# InfraredModule.net
KiCad netlist of a schematic drawn in Altium Designer
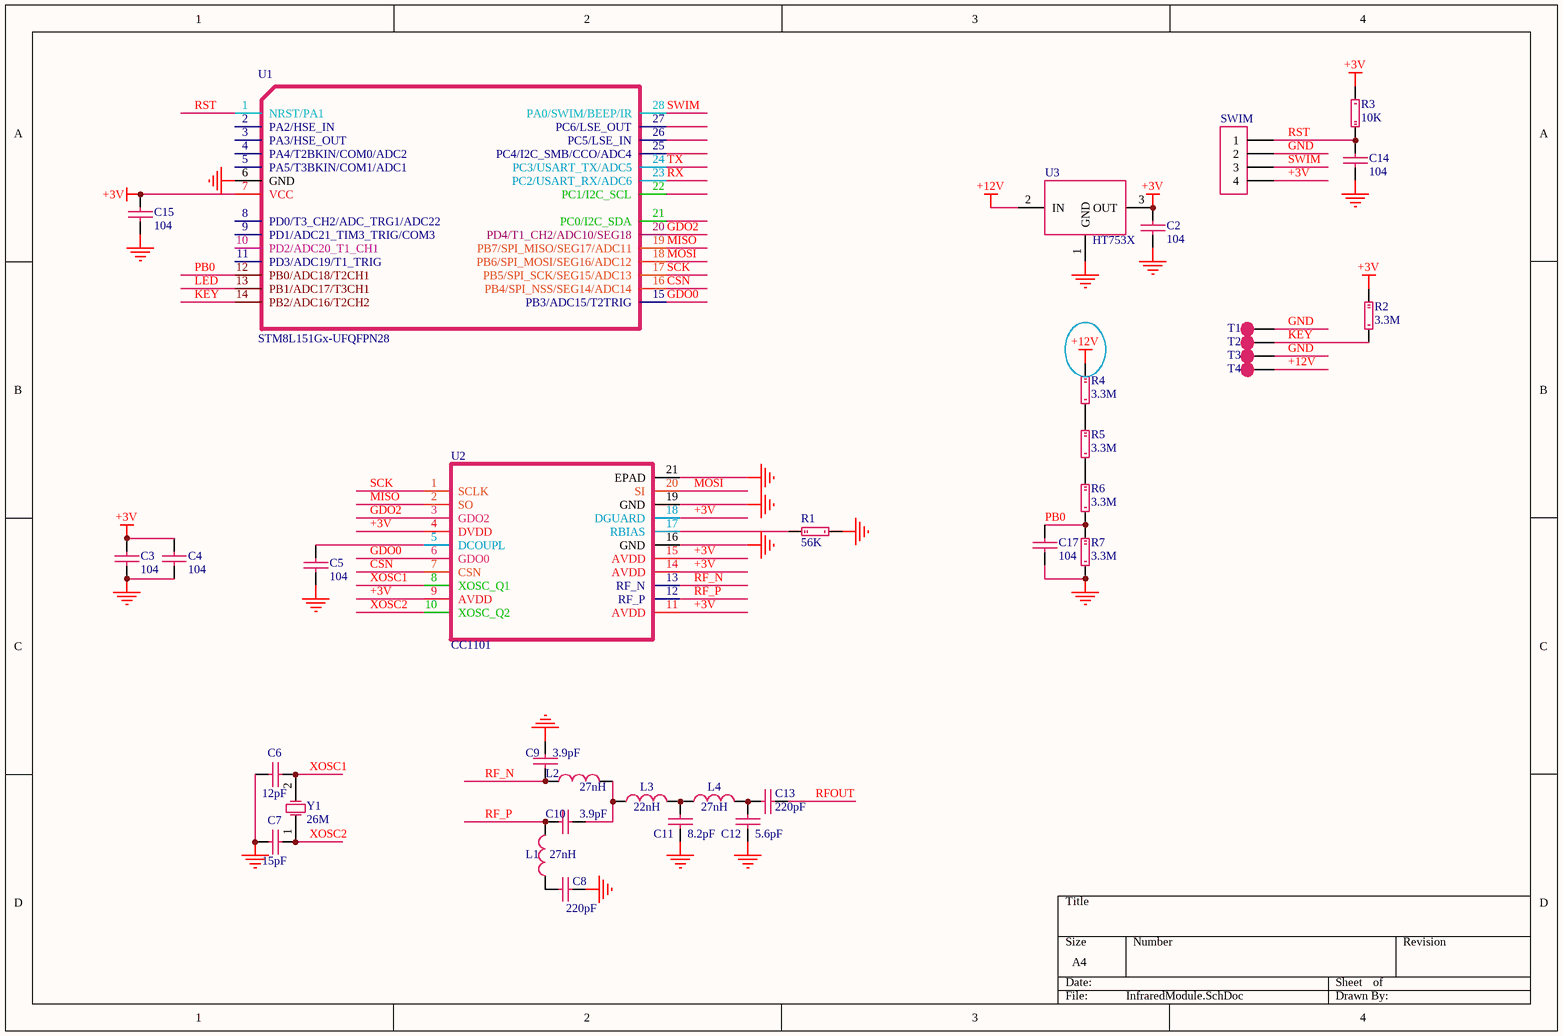
[diagram p0: InfraredModule.SchDoc]

(export (version "E")
  (design (tool "Eeschema 10.0.6"))
  (components
    (comp (ref "C2")
      (value "104")
      (footprint "C0402")
      (description "无极性电容")
      (libsource (lib "Sch_Lib") (part "CAP"))
    )
    (comp (ref "C3")
      (value "104")
      (footprint "C0402")
      (description "无极性电容")
      (libsource (lib "Sch_Lib") (part "CAP"))
    )
    (comp (ref "C4")
      (value "104")
      (footprint "C0402")
      (description "无极性电容")
      (libsource (lib "Sch_Lib") (part "CAP"))
    )
    (comp (ref "C5")
      (value "104")
      (footprint "C0402")
      (description "无极性电容")
      (libsource (lib "Sch_Lib") (part "CAP"))
    )
    (comp (ref "C6")
      (value "12pF")
      (footprint "C0402")
      (description "无极性电容")
      (libsource (lib "Sch_Lib") (part "CAP"))
    )
    (comp (ref "C7")
      (value "15pF")
      (footprint "C0402")
      (description "无极性电容")
      (libsource (lib "Sch_Lib") (part "CAP"))
    )
    (comp (ref "C8")
      (value "220pF")
      (footprint "C0402")
      (description "无极性电容")
      (libsource (lib "Sch_Lib") (part "CAP"))
    )
    (comp (ref "C9")
      (value "3.9pF")
      (footprint "C0402")
      (description "无极性电容")
      (libsource (lib "Sch_Lib") (part "CAP"))
    )
    (comp (ref "C10")
      (value "3.9pF")
      (footprint "C0402")
      (description "无极性电容")
      (libsource (lib "Sch_Lib") (part "CAP"))
    )
    (comp (ref "C11")
      (value "8.2pF")
      (footprint "C0402")
      (description "无极性电容")
      (libsource (lib "Sch_Lib") (part "CAP"))
    )
    (comp (ref "C12")
      (value "5.6pF")
      (footprint "C0402")
      (description "无极性电容")
      (libsource (lib "Sch_Lib") (part "CAP"))
    )
    (comp (ref "C13")
      (value "220pF")
      (footprint "C0402")
      (description "无极性电容")
      (libsource (lib "Sch_Lib") (part "CAP"))
    )
    (comp (ref "C14")
      (value "104")
      (footprint "C0402")
      (description "无极性电容")
      (libsource (lib "Sch_Lib") (part "CAP"))
    )
    (comp (ref "C15")
      (value "104")
      (footprint "C0402")
      (description "无极性电容")
      (libsource (lib "Sch_Lib") (part "CAP"))
    )
    (comp (ref "C17")
      (value "104")
      (footprint "C0402")
      (description "无极性电容")
      (libsource (lib "Sch_Lib") (part "CAP"))
    )
    (comp (ref "L1")
      (value "27nH")
      (footprint "L0402")
      (description "电感")
      (libsource (lib "Sch_Lib") (part "INDUCTOR"))
    )
    (comp (ref "L2")
      (value "27nH")
      (footprint "L0402")
      (description "电感")
      (libsource (lib "Sch_Lib") (part "INDUCTOR"))
    )
    (comp (ref "L3")
      (value "22nH")
      (footprint "L0402")
      (description "电感")
      (libsource (lib "Sch_Lib") (part "INDUCTOR"))
    )
    (comp (ref "L4")
      (value "27nH")
      (footprint "L0402")
      (description "电感")
      (libsource (lib "Sch_Lib") (part "INDUCTOR"))
    )
    (comp (ref "R1")
      (value "56K")
      (footprint "R0402")
      (description "贴片电阻")
      (libsource (lib "Sch_Lib") (part "RES2"))
    )
    (comp (ref "R2")
      (value "3.3M")
      (footprint "R0402")
      (description "贴片电阻")
      (libsource (lib "Sch_Lib") (part "RES2"))
    )
    (comp (ref "R3")
      (value "10K")
      (footprint "R0402")
      (description "贴片电阻")
      (libsource (lib "Sch_Lib") (part "RES2"))
    )
    (comp (ref "R4")
      (value "3.3M")
      (footprint "R0402")
      (description "贴片电阻")
      (libsource (lib "Sch_Lib") (part "RES2"))
    )
    (comp (ref "R5")
      (value "3.3M")
      (footprint "R0402")
      (description "贴片电阻")
      (libsource (lib "Sch_Lib") (part "RES2"))
    )
    (comp (ref "R6")
      (value "3.3M")
      (footprint "R0402")
      (description "贴片电阻")
      (libsource (lib "Sch_Lib") (part "RES2"))
    )
    (comp (ref "R7")
      (value "3.3M")
      (footprint "R0402")
      (description "贴片电阻")
      (libsource (lib "Sch_Lib") (part "RES2"))
    )
    (comp (ref "SWIM") (value "~") (footprint "SIP4-2MM") (libsource (lib "Sch_Lib") (part "HEADER 4X1")))
    (comp (ref "T1")
      (value "~")
      (footprint "TP")
      (description "测试点/触摸点")
      (libsource (lib "Sch_Lib") (part "TP"))
    )
    (comp (ref "T2")
      (value "~")
      (footprint "TP")
      (description "测试点/触摸点")
      (libsource (lib "Sch_Lib") (part "TP"))
    )
    (comp (ref "T3")
      (value "~")
      (footprint "TP")
      (description "测试点/触摸点")
      (libsource (lib "Sch_Lib") (part "TP"))
    )
    (comp (ref "T4")
      (value "~")
      (footprint "TP")
      (description "测试点/触摸点")
      (libsource (lib "Sch_Lib") (part "TP"))
    )
    (comp (ref "U1")
      (value "STM8L151Gx-UFQFPN28")
      (footprint "QFN28-4X4")
      (description "STM8L单片机28引脚,封装UFQFPN28")
      (libsource (lib "Sch_Lib") (part "STM8L151Gx-UFQFPN28"))
    )
    (comp (ref "U2")
      (value "CC1101")
      (footprint "QLP-20")
      (description "RF芯片 TI CC系列")
      (libsource (lib "Sch_Lib") (part "CC1101"))
    )
    (comp (ref "U3")
      (value "HT753X")
      (footprint "SOT-89")
      (description "合泰稳压芯片HT系列")
      (libsource (lib "Sch_Lib") (part "HT753X"))
    )
    (comp (ref "Y1")
      (value "26M")
      (footprint "XTAL-(3.2X2.5MM)-4P")
      (description "晶振")
      (libsource (lib "Sch_Lib") (part "XTAL"))
    )
  )
  (nets
    (net (code "1") (name "+3V") (class "Default")
      (node (ref "C15") (pin "1") (pinfunction "1_1") (pintype "passive"))
      (node (ref "C2") (pin "1") (pinfunction "1_1") (pintype "passive"))
      (node (ref "C3") (pin "1") (pinfunction "1_1") (pintype "passive"))
      (node (ref "C4") (pin "1") (pinfunction "1_1") (pintype "passive"))
      (node (ref "R2") (pin "2") (pinfunction "2_2") (pintype "passive"))
      (node (ref "R3") (pin "1") (pinfunction "1_1") (pintype "passive"))
      (node (ref "SWIM") (pin "4") (pinfunction "4_4") (pintype "passive"))
      (node (ref "U1") (pin "7") (pinfunction "VCC_7") (pintype "passive"))
      (node (ref "U2") (pin "11") (pinfunction "AVDD_11") (pintype "passive"))
      (node (ref "U2") (pin "14") (pinfunction "AVDD_14") (pintype "passive"))
      (node (ref "U2") (pin "15") (pinfunction "AVDD_15") (pintype "passive"))
      (node (ref "U2") (pin "18") (pinfunction "DGUARD_18") (pintype "passive"))
      (node (ref "U2") (pin "4") (pinfunction "DVDD_4") (pintype "passive"))
      (node (ref "U2") (pin "9") (pinfunction "AVDD_9") (pintype "passive"))
      (node (ref "U3") (pin "3") (pinfunction "OUT_3") (pintype "passive"))
    )
    (net (code "2") (name "+12V") (class "Default")
      (node (ref "R4") (pin "2") (pinfunction "2_2") (pintype "passive"))
      (node (ref "T4") (pin "1") (pinfunction "1_1") (pintype "passive"))
      (node (ref "U3") (pin "2") (pinfunction "IN_2") (pintype "passive"))
    )
    (net (code "3") (name "/CSN") (class "Default")
      (node (ref "U1") (pin "16") (pinfunction "PB4/SPI_NSS/SEG14/ADC14_16") (pintype "passive"))
      (node (ref "U2") (pin "7") (pinfunction "CSN_7") (pintype "passive"))
    )
    (net (code "4") (name "/GDO0") (class "Default")
      (node (ref "U1") (pin "15") (pinfunction "PB3/ADC15/T2TRIG_15") (pintype "passive"))
      (node (ref "U2") (pin "6") (pinfunction "GDO0_6") (pintype "passive"))
    )
    (net (code "5") (name "/GDO2") (class "Default")
      (node (ref "U1") (pin "20") (pinfunction "PD4/T1_CH2/ADC10/SEG18_20") (pintype "passive"))
      (node (ref "U2") (pin "3") (pinfunction "GDO2_3") (pintype "passive"))
    )
    (net (code "6") (name "/KEY") (class "Default")
      (node (ref "R2") (pin "1") (pinfunction "1_1") (pintype "passive"))
      (node (ref "T2") (pin "1") (pinfunction "1_1") (pintype "passive"))
      (node (ref "U1") (pin "14") (pinfunction "PB2/ADC16/T2CH2_14") (pintype "passive"))
    )
    (net (code "7") (name "/LED") (class "Default")
      (node (ref "U1") (pin "13") (pinfunction "PB1/ADC17/T3CH1_13") (pintype "passive"))
    )
    (net (code "8") (name "/MISO") (class "Default")
      (node (ref "U1") (pin "19") (pinfunction "PB7/SPI_MISO/SEG17/ADC11_19") (pintype "passive"))
      (node (ref "U2") (pin "2") (pinfunction "SO_2") (pintype "passive"))
    )
    (net (code "9") (name "/MOSI") (class "Default")
      (node (ref "U1") (pin "18") (pinfunction "PB6/SPI_MOSI/SEG16/ADC12_18") (pintype "passive"))
      (node (ref "U2") (pin "20") (pinfunction "SI_20") (pintype "passive"))
    )
    (net (code "10") (name "/PB0") (class "Default")
      (node (ref "C17") (pin "1") (pinfunction "1_1") (pintype "passive"))
      (node (ref "R6") (pin "1") (pinfunction "1_1") (pintype "passive"))
      (node (ref "R7") (pin "2") (pinfunction "2_2") (pintype "passive"))
      (node (ref "U1") (pin "12") (pinfunction "PB0/ADC18/T2CH1_12") (pintype "passive"))
    )
    (net (code "11") (name "/RFOUT") (class "Default")
      (node (ref "C13") (pin "2") (pinfunction "2_2") (pintype "passive"))
    )
    (net (code "12") (name "/RF_N") (class "Default")
      (node (ref "C9") (pin "2") (pinfunction "2_2") (pintype "passive"))
      (node (ref "L2") (pin "1") (pinfunction "1_1") (pintype "passive"))
      (node (ref "U2") (pin "13") (pinfunction "RF_N_13") (pintype "passive"))
    )
    (net (code "13") (name "/RF_P") (class "Default")
      (node (ref "C10") (pin "2") (pinfunction "2_2") (pintype "passive"))
      (node (ref "L1") (pin "2") (pinfunction "2_2") (pintype "passive"))
      (node (ref "U2") (pin "12") (pinfunction "RF_P_12") (pintype "passive"))
    )
    (net (code "14") (name "/RST") (class "Default")
      (node (ref "C14") (pin "1") (pinfunction "1_1") (pintype "passive"))
      (node (ref "R3") (pin "2") (pinfunction "2_2") (pintype "passive"))
      (node (ref "SWIM") (pin "1") (pinfunction "1_1") (pintype "passive"))
      (node (ref "U1") (pin "1") (pinfunction "NRST/PA1_1") (pintype "passive"))
    )
    (net (code "15") (name "/RX") (class "Default")
      (node (ref "U1") (pin "23") (pinfunction "PC2/USART_RX/ADC6_23") (pintype "passive"))
    )
    (net (code "16") (name "/SCK") (class "Default")
      (node (ref "U1") (pin "17") (pinfunction "PB5/SPI_SCK/SEG15/ADC13_17") (pintype "passive"))
      (node (ref "U2") (pin "1") (pinfunction "SCLK_1") (pintype "passive"))
    )
    (net (code "17") (name "/SWIM") (class "Default")
      (node (ref "SWIM") (pin "3") (pinfunction "3_3") (pintype "passive"))
      (node (ref "U1") (pin "28") (pinfunction "PA0/SWIM/BEEP/IR_28") (pintype "passive"))
    )
    (net (code "18") (name "/TX") (class "Default")
      (node (ref "U1") (pin "24") (pinfunction "PC3/USART_TX/ADC5_24") (pintype "passive"))
    )
    (net (code "19") (name "/XOSC1") (class "Default")
      (node (ref "C6") (pin "1") (pinfunction "1_1") (pintype "passive"))
      (node (ref "U2") (pin "8") (pinfunction "XOSC_Q1_8") (pintype "passive"))
      (node (ref "Y1") (pin "2") (pinfunction "OSC2_2") (pintype "passive"))
    )
    (net (code "20") (name "/XOSC2") (class "Default")
      (node (ref "C7") (pin "1") (pinfunction "1_1") (pintype "passive"))
      (node (ref "U2") (pin "10") (pinfunction "XOSC_Q2_10") (pintype "passive"))
      (node (ref "Y1") (pin "1") (pinfunction "OSC1_1") (pintype "passive"))
    )
    (net (code "21") (name "GND") (class "Default")
      (node (ref "C11") (pin "2") (pinfunction "2_2") (pintype "passive"))
      (node (ref "C12") (pin "2") (pinfunction "2_2") (pintype "passive"))
      (node (ref "C14") (pin "2") (pinfunction "2_2") (pintype "passive"))
      (node (ref "C15") (pin "2") (pinfunction "2_2") (pintype "passive"))
      (node (ref "C17") (pin "2") (pinfunction "2_2") (pintype "passive"))
      (node (ref "C2") (pin "2") (pinfunction "2_2") (pintype "passive"))
      (node (ref "C3") (pin "2") (pinfunction "2_2") (pintype "passive"))
      (node (ref "C4") (pin "2") (pinfunction "2_2") (pintype "passive"))
      (node (ref "C5") (pin "1") (pinfunction "1_1") (pintype "passive"))
      (node (ref "C6") (pin "2") (pinfunction "2_2") (pintype "passive"))
      (node (ref "C7") (pin "2") (pinfunction "2_2") (pintype "passive"))
      (node (ref "C8") (pin "2") (pinfunction "2_2") (pintype "passive"))
      (node (ref "C9") (pin "1") (pinfunction "1_1") (pintype "passive"))
      (node (ref "R1") (pin "1") (pinfunction "1_1") (pintype "passive"))
      (node (ref "R7") (pin "1") (pinfunction "1_1") (pintype "passive"))
      (node (ref "SWIM") (pin "2") (pinfunction "2_2") (pintype "passive"))
      (node (ref "T1") (pin "1") (pinfunction "1_1") (pintype "passive"))
      (node (ref "T3") (pin "1") (pinfunction "1_1") (pintype "passive"))
      (node (ref "U1") (pin "6") (pinfunction "GND_6") (pintype "passive"))
      (node (ref "U2") (pin "16") (pinfunction "GND_16") (pintype "passive"))
      (node (ref "U2") (pin "19") (pinfunction "GND_19") (pintype "passive"))
      (node (ref "U2") (pin "21") (pinfunction "EPAD_21") (pintype "passive"))
      (node (ref "U3") (pin "1") (pinfunction "GND_1") (pintype "passive"))
    )
    (net (code "22") (name "Net-(C8-Pad1)") (class "Default")
      (node (ref "C8") (pin "1") (pinfunction "1_1") (pintype "passive"))
      (node (ref "L1") (pin "1") (pinfunction "1_1") (pintype "passive"))
    )
    (net (code "23") (name "Net-(C10-Pad1)") (class "Default")
      (node (ref "C10") (pin "1") (pinfunction "1_1") (pintype "passive"))
      (node (ref "L2") (pin "2") (pinfunction "2_2") (pintype "passive"))
      (node (ref "L3") (pin "1") (pinfunction "1_1") (pintype "passive"))
    )
    (net (code "24") (name "Net-(C11-Pad1)") (class "Default")
      (node (ref "C11") (pin "1") (pinfunction "1_1") (pintype "passive"))
      (node (ref "L3") (pin "2") (pinfunction "2_2") (pintype "passive"))
      (node (ref "L4") (pin "1") (pinfunction "1_1") (pintype "passive"))
    )
    (net (code "25") (name "Net-(C12-Pad1)") (class "Default")
      (node (ref "C12") (pin "1") (pinfunction "1_1") (pintype "passive"))
      (node (ref "C13") (pin "1") (pinfunction "1_1") (pintype "passive"))
      (node (ref "L4") (pin "2") (pinfunction "2_2") (pintype "passive"))
    )
    (net (code "26") (name "Net-(R4-Pad1)") (class "Default")
      (node (ref "R4") (pin "1") (pinfunction "1_1") (pintype "passive"))
      (node (ref "R5") (pin "2") (pinfunction "2_2") (pintype "passive"))
    )
    (net (code "27") (name "Net-(R5-Pad1)") (class "Default")
      (node (ref "R5") (pin "1") (pinfunction "1_1") (pintype "passive"))
      (node (ref "R6") (pin "2") (pinfunction "2_2") (pintype "passive"))
    )
    (net (code "28") (name "Net-(U2-DCOUPL)") (class "Default")
      (node (ref "C5") (pin "2") (pinfunction "2_2") (pintype "passive"))
      (node (ref "U2") (pin "5") (pinfunction "DCOUPL_5") (pintype "passive"))
    )
    (net (code "29") (name "Net-(U2-RBIAS)") (class "Default")
      (node (ref "R1") (pin "2") (pinfunction "2_2") (pintype "passive"))
      (node (ref "U2") (pin "17") (pinfunction "RBIAS_17") (pintype "passive"))
    )
    (net (code "30") (name "unconnected-(U1-PA2{slash}HSE_IN-Pad2)") (class "Default")
      (node (ref "U1") (pin "2") (pinfunction "PA2/HSE_IN_2") (pintype "passive"))
    )
    (net (code "31") (name "unconnected-(U1-PA3{slash}HSE_OUT-Pad3)") (class "Default")
      (node (ref "U1") (pin "3") (pinfunction "PA3/HSE_OUT_3") (pintype "passive"))
    )
    (net (code "32") (name "unconnected-(U1-PA4{slash}T2BKIN{slash}COM0{slash}ADC2-Pad4)") (class "Default")
      (node (ref "U1") (pin "4") (pinfunction "PA4/T2BKIN/COM0/ADC2_4") (pintype "passive"))
    )
    (net (code "33") (name "unconnected-(U1-PA5{slash}T3BKIN{slash}COM1{slash}ADC1-Pad5)") (class "Default")
      (node (ref "U1") (pin "5") (pinfunction "PA5/T3BKIN/COM1/ADC1_5") (pintype "passive"))
    )
    (net (code "34") (name "unconnected-(U1-PC0{slash}I2C_SDA-Pad21)") (class "Default")
      (node (ref "U1") (pin "21") (pinfunction "PC0/I2C_SDA_21") (pintype "passive"))
    )
    (net (code "35") (name "unconnected-(U1-PC1{slash}I2C_SCL-Pad22)") (class "Default")
      (node (ref "U1") (pin "22") (pinfunction "PC1/I2C_SCL_22") (pintype "passive"))
    )
    (net (code "36") (name "unconnected-(U1-PC4{slash}I2C_SMB{slash}CCO{slash}ADC4-Pad25)") (class "Default")
      (node (ref "U1") (pin "25") (pinfunction "PC4/I2C_SMB/CCO/ADC4_25") (pintype "passive"))
    )
    (net (code "37") (name "unconnected-(U1-PC5{slash}LSE_IN-Pad26)") (class "Default")
      (node (ref "U1") (pin "26") (pinfunction "PC5/LSE_IN_26") (pintype "passive"))
    )
    (net (code "38") (name "unconnected-(U1-PC6{slash}LSE_OUT-Pad27)") (class "Default")
      (node (ref "U1") (pin "27") (pinfunction "PC6/LSE_OUT_27") (pintype "passive"))
    )
    (net (code "39") (name "unconnected-(U1-PD0{slash}T3_CH2{slash}ADC_TRG1{slash}ADC22-Pad8)") (class "Default")
      (node (ref "U1") (pin "8") (pinfunction "PD0/T3_CH2/ADC_TRG1/ADC22_8") (pintype "passive"))
    )
    (net (code "40") (name "unconnected-(U1-PD1{slash}ADC21_TIM3_TRIG{slash}COM3-Pad9)") (class "Default")
      (node (ref "U1") (pin "9") (pinfunction "PD1/ADC21_TIM3_TRIG/COM3_9") (pintype "passive"))
    )
    (net (code "41") (name "unconnected-(U1-PD2{slash}ADC20_T1_CH1-Pad10)") (class "Default")
      (node (ref "U1") (pin "10") (pinfunction "PD2/ADC20_T1_CH1_10") (pintype "passive"))
    )
    (net (code "42") (name "unconnected-(U1-PD3{slash}ADC19{slash}T1_TRIG-Pad11)") (class "Default")
      (node (ref "U1") (pin "11") (pinfunction "PD3/ADC19/T1_TRIG_11") (pintype "passive"))
    )
  )
)
